# Mosfet_Driver.net
KiCad netlist of a schematic drawn in Altium Designer
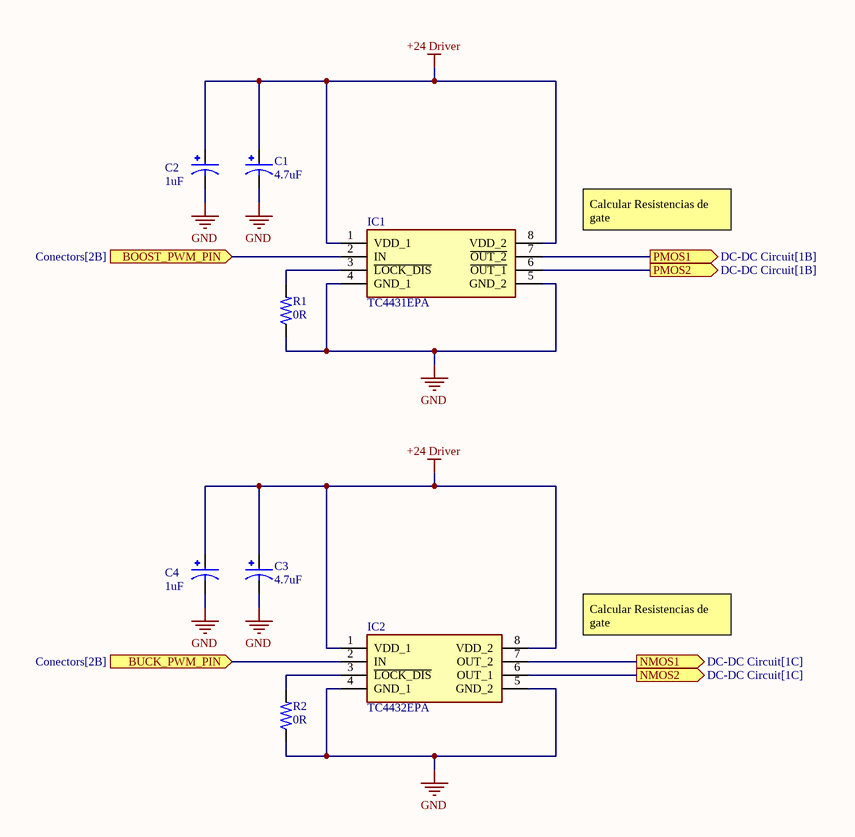
[diagram p0: Mosfet Driver.SchDoc]

(export (version "E")
  (design (tool "Eeschema 10.0.6"))
  (components
    (comp (ref "C1")
      (value "4.7uF")
      (footprint "Capacitors SMD:Electrolytic 4x5.4")
      (fields (field (name "MF") "Panasonic") (field (name "MP") "EEE-HA1E100WR"))
      (libsource (lib "Capacitors SMD") (part "Electrolytic 4x5.4"))
    )
    (comp (ref "C2")
      (value "1uF")
      (footprint "Capacitors SMD:Electrolytic 4x5.4")
      (fields (field (name "MF") "Panasonic") (field (name "MP") "EEE-HA1E100WR"))
      (libsource (lib "Capacitors SMD") (part "Electrolytic 4x5.4"))
    )
    (comp (ref "C3")
      (value "4.7uF")
      (footprint "Capacitors SMD:Electrolytic 4x5.4")
      (fields (field (name "MF") "Panasonic") (field (name "MP") "EEE-HA1E100WR"))
      (libsource (lib "Capacitors SMD") (part "Electrolytic 4x5.4"))
    )
    (comp (ref "C4")
      (value "1uF")
      (footprint "Capacitors SMD:Electrolytic 4x5.4")
      (fields (field (name "MF") "Panasonic") (field (name "MP") "EEE-HA1E100WR"))
      (libsource (lib "Capacitors SMD") (part "Electrolytic 4x5.4"))
    )
    (comp (ref "IC1")
      (value "TC4431EPA")
      (footprint "SamacSys:DIP781W56P254L950H533Q8N")
      (description "Integrated Circuit")
      (fields (field (name "MOUSER PART NUMBER") "579-TC4431EPA"))
      (libsource (lib "*") (part "TC4431EPA"))
    )
    (comp (ref "IC2")
      (value "TC4432EPA")
      (footprint "SamacSys:DIP781W56P254L950H533Q8N")
      (description "Integrated Circuit")
      (fields (field (name "MOUSER PART NUMBER") "579-TC4432EPA"))
      (libsource (lib "*") (part "TC4432EPA"))
    )
    (comp (ref "R1")
      (value "0R")
      (footprint "0805")
      (fields
        (field (name "MP") "2-2176053-0")
        (field (name "TOLERANCE") "1%")
        (field (name "MF") "TE Connectivity")
      )
      (libsource (lib "Resistors SMD") (part "0805_Resistor"))
    )
    (comp (ref "R2")
      (value "0R")
      (footprint "0805")
      (fields
        (field (name "MP") "2-2176053-0")
        (field (name "TOLERANCE") "1%")
        (field (name "MF") "TE Connectivity")
      )
      (libsource (lib "Resistors SMD") (part "0805_Resistor"))
    )
  )
  (nets
    (net (code "1") (name "+24 Driver") (class "Default")
      (node (ref "C1") (pin "1") (pinfunction "1_1") (pintype "passive"))
      (node (ref "C2") (pin "1") (pinfunction "1_1") (pintype "passive"))
      (node (ref "C3") (pin "1") (pinfunction "1_1") (pintype "passive"))
      (node (ref "C4") (pin "1") (pinfunction "1_1") (pintype "passive"))
      (node (ref "IC1") (pin "1") (pinfunction "VDD_1_1") (pintype "passive"))
      (node (ref "IC1") (pin "8") (pinfunction "VDD_2_8") (pintype "passive"))
      (node (ref "IC2") (pin "1") (pinfunction "VDD_1_1") (pintype "passive"))
      (node (ref "IC2") (pin "8") (pinfunction "VDD_2_8") (pintype "passive"))
    )
    (net (code "2") (name "/BOOST_PWM_PIN") (class "Default")
      (node (ref "IC1") (pin "2") (pinfunction "IN_2") (pintype "passive"))
    )
    (net (code "3") (name "/BUCK_PWM_PIN") (class "Default")
      (node (ref "IC2") (pin "2") (pinfunction "IN_2") (pintype "passive"))
    )
    (net (code "4") (name "/NMOS1") (class "Default")
      (node (ref "IC2") (pin "7") (pinfunction "OUT_2_7") (pintype "passive"))
    )
    (net (code "5") (name "/NMOS2") (class "Default")
      (node (ref "IC2") (pin "6") (pinfunction "OUT_1_6") (pintype "passive"))
    )
    (net (code "6") (name "/PMOS1") (class "Default")
      (node (ref "IC1") (pin "7") (pinfunction "~{OUT_2}_7") (pintype "passive"))
    )
    (net (code "7") (name "/PMOS2") (class "Default")
      (node (ref "IC1") (pin "6") (pinfunction "~{OUT_1}_6") (pintype "passive"))
    )
    (net (code "8") (name "GND") (class "Default")
      (node (ref "C1") (pin "2") (pinfunction "2_2") (pintype "passive"))
      (node (ref "C2") (pin "2") (pinfunction "2_2") (pintype "passive"))
      (node (ref "C3") (pin "2") (pinfunction "2_2") (pintype "passive"))
      (node (ref "C4") (pin "2") (pinfunction "2_2") (pintype "passive"))
      (node (ref "IC1") (pin "4") (pinfunction "GND_1_4") (pintype "passive"))
      (node (ref "IC1") (pin "5") (pinfunction "GND_2_5") (pintype "passive"))
      (node (ref "IC2") (pin "4") (pinfunction "GND_1_4") (pintype "passive"))
      (node (ref "IC2") (pin "5") (pinfunction "GND_2_5") (pintype "passive"))
      (node (ref "R1") (pin "1") (pinfunction "1_1") (pintype "passive"))
      (node (ref "R2") (pin "1") (pinfunction "1_1") (pintype "passive"))
    )
    (net (code "9") (name "Net-(IC1-~{LOCK_DIS})") (class "Default")
      (node (ref "IC1") (pin "3") (pinfunction "~{LOCK_DIS}_3") (pintype "passive"))
      (node (ref "R1") (pin "2") (pinfunction "2_2") (pintype "passive"))
    )
    (net (code "10") (name "Net-(IC2-~{LOCK_DIS})") (class "Default")
      (node (ref "IC2") (pin "3") (pinfunction "~{LOCK_DIS}_3") (pintype "passive"))
      (node (ref "R2") (pin "2") (pinfunction "2_2") (pintype "passive"))
    )
  )
)
